# Temp_Schematic.net
KiCad netlist of a schematic drawn in EAGLE
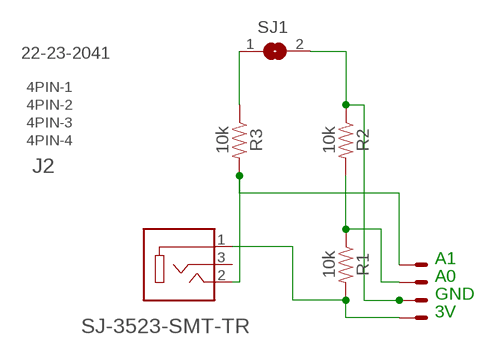
[diagram p0: schematic, sheet 1]

(export (version "E")
  (design (tool "Eeschema 10.0.6"))
  (components
    (comp (ref "4PIN")
      (value "22-23-2041")
      (footprint "eagle-import:22-23-2041")
      (fields (field (name "MF") "MOLEX"))
      (libsource (lib "eagle-import") (part "22-23-2041"))
    )
    (comp (ref "J2")
      (value "SJ-3523-SMT-TR")
      (footprint "eagle-import:CUI_SJ-3523-SMT-TR")
      (fields (field (name "MF") "CUI Devices"))
      (libsource (lib "eagle-import") (part "SJ-3523-SMT-TR"))
    )
    (comp (ref "R1")
      (value "10k")
      (footprint "eagle-import:AXIAL-0.3")
      (libsource (lib "eagle-import") (part "10KOHM-HORIZ-1/4W-5%"))
    )
    (comp (ref "R2")
      (value "10k")
      (footprint "eagle-import:AXIAL-0.3")
      (libsource (lib "eagle-import") (part "10KOHM-HORIZ-1/4W-5%"))
    )
    (comp (ref "R3")
      (value "10k")
      (footprint "eagle-import:AXIAL-0.3")
      (libsource (lib "eagle-import") (part "10KOHM-HORIZ-1/4W-5%"))
    )
    (comp (ref "SJ1") (value "SJ") (footprint "eagle-import:SJ") (libsource (lib "eagle-import") (part "SJ")))
  )
  (nets
    (net (code "1") (name "Net-(4PINA-S)") (class "Default")
      (node (ref "4PIN") (pin "1") (pinfunction "S_1") (pintype "passive"))
      (node (ref "J2") (pin "2") (pinfunction "2_2") (pintype "passive"))
      (node (ref "R3") (pin "P$2") (pinfunction "2_P$2") (pintype "passive"))
    )
    (net (code "2") (name "Net-(4PINB-S)") (class "Default")
      (node (ref "4PIN") (pin "2") (pinfunction "S_2") (pintype "passive"))
      (node (ref "R1") (pin "P$1") (pinfunction "1_P$1") (pintype "passive"))
      (node (ref "R2") (pin "P$2") (pinfunction "2_P$2") (pintype "passive"))
    )
    (net (code "3") (name "Net-(4PINC-S)") (class "Default")
      (node (ref "4PIN") (pin "3") (pinfunction "S_3") (pintype "passive"))
      (node (ref "R2") (pin "P$1") (pinfunction "1_P$1") (pintype "passive"))
      (node (ref "SJ1") (pin "2") (pinfunction "2_2") (pintype "passive"))
    )
    (net (code "4") (name "Net-(4PIND-S)") (class "Default")
      (node (ref "4PIN") (pin "4") (pinfunction "S_4") (pintype "passive"))
      (node (ref "J2") (pin "1") (pinfunction "1_1") (pintype "passive"))
      (node (ref "R1") (pin "P$2") (pinfunction "2_P$2") (pintype "passive"))
    )
    (net (code "5") (name "Net-(R3-1)") (class "Default")
      (node (ref "R3") (pin "P$1") (pinfunction "1_P$1") (pintype "passive"))
      (node (ref "SJ1") (pin "1") (pinfunction "1_1") (pintype "passive"))
    )
    (net (code "6") (name "unconnected-(J2-Pad3)") (class "Default")
      (node (ref "J2") (pin "3") (pinfunction "3_3") (pintype "passive"))
    )
  )
)
